# BLE.net
KiCad netlist of a schematic drawn in Altium Designer
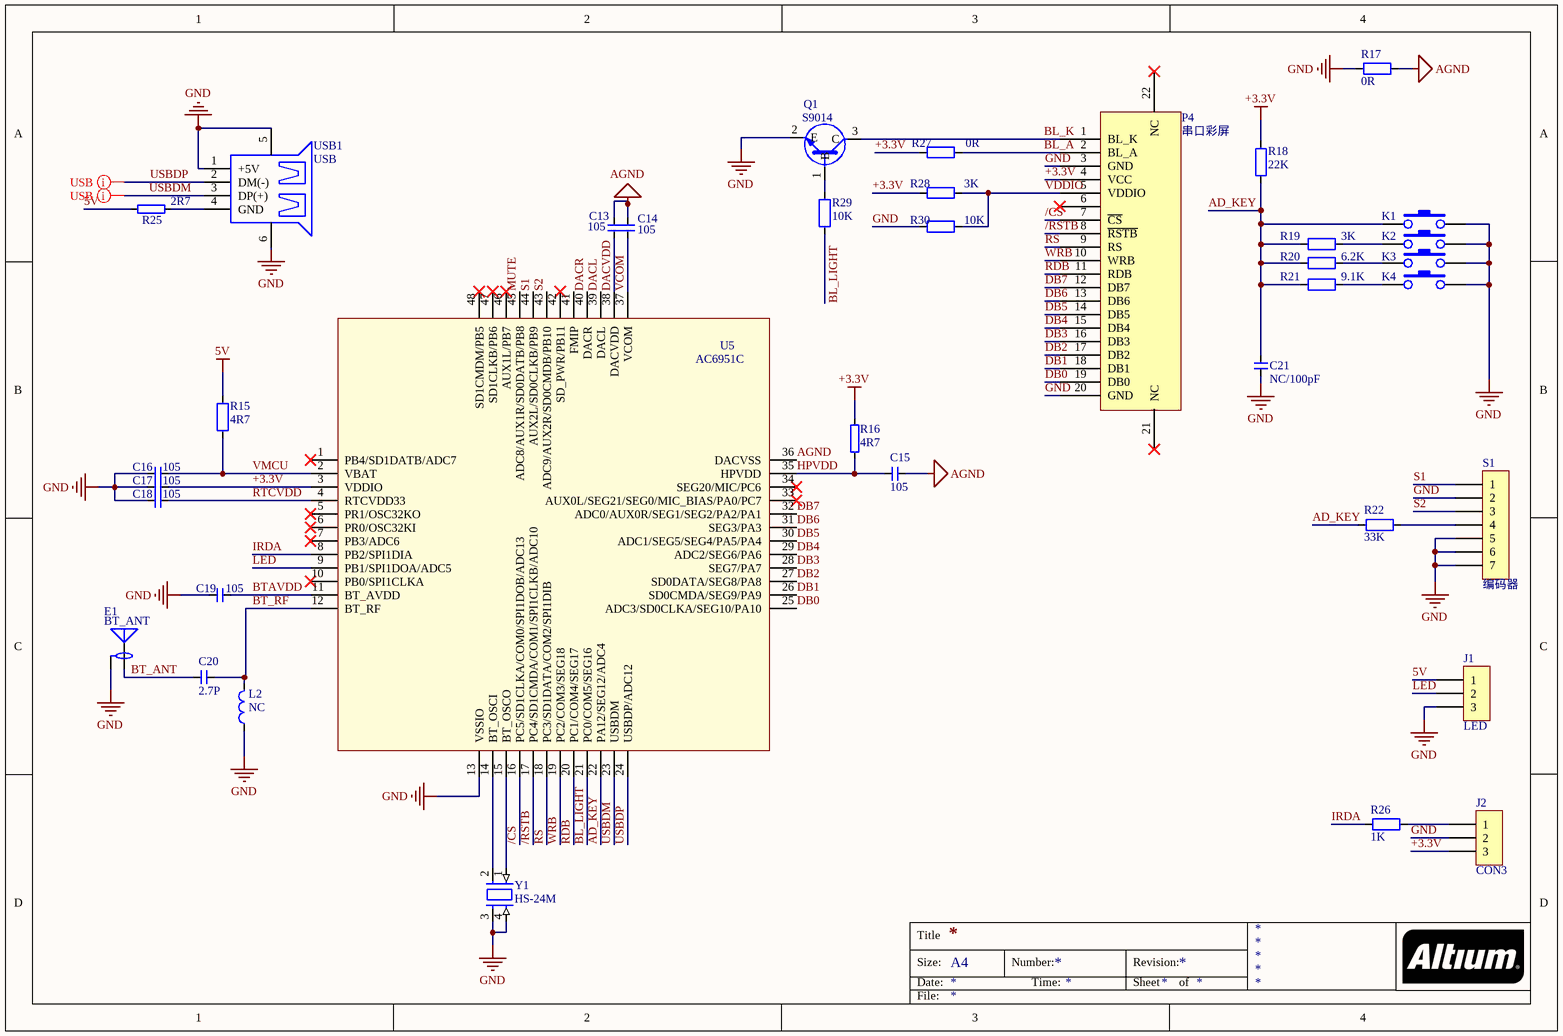
[diagram p0: BLE主控原理图.SchDoc]

(export (version "E")
  (design (tool "Eeschema 10.0.6"))
  (components
    (comp (ref "C13") (value "105") (footprint "C0603") (libsource (lib "MY") (part "CAP-0603")))
    (comp (ref "C14") (value "105") (footprint "C0603") (libsource (lib "MY") (part "CAP-0603")))
    (comp (ref "C15") (value "105") (footprint "C0603") (libsource (lib "MY") (part "CAP-0603")))
    (comp (ref "C16") (value "105") (footprint "C0603") (libsource (lib "MY") (part "CAP-0603")))
    (comp (ref "C17") (value "105") (footprint "C0603") (libsource (lib "MY") (part "CAP-0603")))
    (comp (ref "C18") (value "105") (footprint "C0603") (libsource (lib "MY") (part "CAP-0603")))
    (comp (ref "C19") (value "105") (footprint "C0603") (libsource (lib "MY") (part "CAP-0603")))
    (comp (ref "C20") (value "2.7P") (footprint "C0603") (libsource (lib "MY") (part "CAP-0603")))
    (comp (ref "C21") (value "NC/100pF") (footprint "C0603") (libsource (lib "MY") (part "CAP-0603")))
    (comp (ref "E1") (value "BT_ANT") (footprint "新F天线") (libsource (lib "常用原理图库") (part "BT_ANT")))
    (comp (ref "J1")
      (value "LED")
      (footprint "CON-3X2.54")
      (description "Connector")
      (libsource (lib "插件") (part "CON3"))
    )
    (comp (ref "J2")
      (value "CON3")
      (footprint "CON-3X2.54")
      (description "Connector")
      (libsource (lib "插件") (part "CON3"))
    )
    (comp (ref "K1") (value "~") (footprint "KEY") (libsource (lib "MY") (part "Key")))
    (comp (ref "K2") (value "~") (footprint "KEY") (libsource (lib "MY") (part "Key")))
    (comp (ref "K3") (value "~") (footprint "KEY") (libsource (lib "MY") (part "Key")))
    (comp (ref "K4") (value "~") (footprint "KEY") (libsource (lib "MY") (part "Key")))
    (comp (ref "L2") (value "NC") (footprint "L0603") (libsource (lib "MY") (part "L")))
    (comp (ref "P4") (value "串口彩屏") (footprint "FFC-P20-1MM") (libsource (lib "MY") (part "LCD-20P")))
    (comp (ref "Q1") (value "S9014") (footprint "SOT23") (libsource (lib "MY") (part "NPN")))
    (comp (ref "R15") (value "4R7") (footprint "R0805") (libsource (lib "MY") (part "RES-0603")))
    (comp (ref "R16") (value "4R7") (footprint "R0603") (libsource (lib "电阻") (part "RES")))
    (comp (ref "R17") (value "0R") (footprint "R0603") (libsource (lib "MY") (part "RES-0603")))
    (comp (ref "R18") (value "22K") (footprint "R0603") (libsource (lib "MY") (part "RES-0603")))
    (comp (ref "R19") (value "3K") (footprint "R0603") (libsource (lib "MY") (part "RES-0603")))
    (comp (ref "R20") (value "6.2K") (footprint "R0603") (libsource (lib "MY") (part "RES-0603")))
    (comp (ref "R21") (value "9.1K") (footprint "R0603") (libsource (lib "MY") (part "RES-0603")))
    (comp (ref "R22") (value "33K") (footprint "R0603") (libsource (lib "MY") (part "RES-0603")))
    (comp (ref "R25") (value "2R7") (footprint "R0603") (libsource (lib "电阻") (part "RES")))
    (comp (ref "R26") (value "1K") (footprint "R0603") (libsource (lib "MY") (part "RES-0603")))
    (comp (ref "R27") (value "0R") (footprint "R0603") (libsource (lib "MY") (part "RES-0603")))
    (comp (ref "R28") (value "3K") (footprint "R0603") (libsource (lib "MY") (part "RES-0603")))
    (comp (ref "R29") (value "10K") (footprint "R0603") (libsource (lib "MY") (part "RES-0603")))
    (comp (ref "R30") (value "10K") (footprint "R0603") (libsource (lib "MY") (part "RES-0603")))
    (comp (ref "S1")
      (value "编码器")
      (footprint "BMQ+PUSH")
      (description "Connector")
      (libsource (lib "插件") (part "CON7"))
    )
    (comp (ref "U5") (value "AC6951C") (footprint "LQFP48") (libsource (lib "MY") (part "AC6951C")))
    (comp (ref "USB1") (value "USB") (footprint "USBSMT") (libsource (lib "常用原理图库") (part "USB")))
    (comp (ref "Y1") (value "HS-24M") (footprint "JZ") (libsource (lib "常用原理图库") (part "CRYSTAL")))
  )
  (nets
    (net (code "1") (name "+3.3V") (class "Default")
      (node (ref "C17") (pin "2") (pinfunction "2_2") (pintype "passive"))
      (node (ref "J2") (pin "3") (pinfunction "3_3") (pintype "passive"))
      (node (ref "P4") (pin "4") (pinfunction "VCC_4") (pintype "passive"))
      (node (ref "R16") (pin "2") (pinfunction "2_2") (pintype "passive"))
      (node (ref "R18") (pin "2") (pinfunction "2_2") (pintype "passive"))
      (node (ref "R27") (pin "1") (pinfunction "1_1") (pintype "passive"))
      (node (ref "R28") (pin "2") (pinfunction "2_2") (pintype "passive"))
      (node (ref "U5") (pin "3") (pinfunction "VDDIO_3") (pintype "passive"))
    )
    (net (code "2") (name "/AD_KEY") (class "Default")
      (node (ref "C21") (pin "1") (pinfunction "1_1") (pintype "passive"))
      (node (ref "K1") (pin "1") (pinfunction "1_1") (pintype "passive"))
      (node (ref "R18") (pin "1") (pinfunction "1_1") (pintype "passive"))
      (node (ref "R19") (pin "1") (pinfunction "1_1") (pintype "passive"))
      (node (ref "R20") (pin "1") (pinfunction "1_1") (pintype "passive"))
      (node (ref "R21") (pin "1") (pinfunction "1_1") (pintype "passive"))
      (node (ref "R22") (pin "1") (pinfunction "1_1") (pintype "passive"))
      (node (ref "U5") (pin "22") (pinfunction "PA12/SEG12/ADC4_22") (pintype "passive"))
    )
    (net (code "3") (name "/BL_A") (class "Default")
      (node (ref "P4") (pin "2") (pinfunction "BL_A_2") (pintype "passive"))
      (node (ref "R27") (pin "2") (pinfunction "2_2") (pintype "passive"))
    )
    (net (code "4") (name "/BL_K") (class "Default")
      (node (ref "P4") (pin "1") (pinfunction "BL_K_1") (pintype "passive"))
      (node (ref "Q1") (pin "3") (pinfunction "C_3") (pintype "passive"))
    )
    (net (code "5") (name "/BL_LIGHT") (class "Default")
      (node (ref "R29") (pin "1") (pinfunction "1_1") (pintype "passive"))
      (node (ref "U5") (pin "21") (pinfunction "PC0/COM5/SEG16_21") (pintype "passive"))
    )
    (net (code "6") (name "/BTAVDD") (class "Default")
      (node (ref "C19") (pin "2") (pinfunction "2_2") (pintype "passive"))
      (node (ref "U5") (pin "11") (pinfunction "BT_AVDD_11") (pintype "passive"))
    )
    (net (code "7") (name "/BT_ANT") (class "Default")
      (node (ref "C20") (pin "1") (pinfunction "1_1") (pintype "passive"))
      (node (ref "E1") (pin "1") (pinfunction "1_1") (pintype "passive"))
    )
    (net (code "8") (name "/BT_RF") (class "Default")
      (node (ref "C20") (pin "2") (pinfunction "2_2") (pintype "passive"))
      (node (ref "L2") (pin "2") (pinfunction "2_2") (pintype "passive"))
      (node (ref "U5") (pin "12") (pinfunction "BT_RF_12") (pintype "passive"))
    )
    (net (code "9") (name "/DACL") (class "Default")
      (node (ref "U5") (pin "39") (pinfunction "DACL_39") (pintype "passive"))
    )
    (net (code "10") (name "/DACR") (class "Default")
      (node (ref "U5") (pin "40") (pinfunction "DACR_40") (pintype "passive"))
    )
    (net (code "11") (name "/DACVDD") (class "Default")
      (node (ref "C13") (pin "1") (pinfunction "1_1") (pintype "passive"))
      (node (ref "U5") (pin "38") (pinfunction "DACVDD_38") (pintype "passive"))
    )
    (net (code "12") (name "/DB0") (class "Default")
      (node (ref "P4") (pin "19") (pinfunction "DB0_19") (pintype "passive"))
      (node (ref "U5") (pin "25") (pinfunction "ADC3/SD0CLKA/SEG10/PA10_25") (pintype "passive"))
    )
    (net (code "13") (name "/DB1") (class "Default")
      (node (ref "P4") (pin "18") (pinfunction "DB1_18") (pintype "passive"))
      (node (ref "U5") (pin "26") (pinfunction "SD0CMDA/SEG9/PA9_26") (pintype "passive"))
    )
    (net (code "14") (name "/DB2") (class "Default")
      (node (ref "P4") (pin "17") (pinfunction "DB2_17") (pintype "passive"))
      (node (ref "U5") (pin "27") (pinfunction "SD0DATA/SEG8/PA8_27") (pintype "passive"))
    )
    (net (code "15") (name "/DB3") (class "Default")
      (node (ref "P4") (pin "16") (pinfunction "DB3_16") (pintype "passive"))
      (node (ref "U5") (pin "28") (pinfunction "SEG7/PA7_28") (pintype "passive"))
    )
    (net (code "16") (name "/DB4") (class "Default")
      (node (ref "P4") (pin "15") (pinfunction "DB4_15") (pintype "passive"))
      (node (ref "U5") (pin "29") (pinfunction "ADC2/SEG6/PA6_29") (pintype "passive"))
    )
    (net (code "17") (name "/DB5") (class "Default")
      (node (ref "P4") (pin "14") (pinfunction "DB5_14") (pintype "passive"))
      (node (ref "U5") (pin "30") (pinfunction "ADC1/SEG5/SEG4/PA5/PA4_30") (pintype "passive"))
    )
    (net (code "18") (name "/DB6") (class "Default")
      (node (ref "P4") (pin "13") (pinfunction "DB6_13") (pintype "passive"))
      (node (ref "U5") (pin "31") (pinfunction "SEG3/PA3_31") (pintype "passive"))
    )
    (net (code "19") (name "/DB7") (class "Default")
      (node (ref "P4") (pin "12") (pinfunction "DB7_12") (pintype "passive"))
      (node (ref "U5") (pin "32") (pinfunction "ADC0/AUX0R/SEG1/SEG2/PA2/PA1_32") (pintype "passive"))
    )
    (net (code "20") (name "/HPVDD") (class "Default")
      (node (ref "C15") (pin "2") (pinfunction "2_2") (pintype "passive"))
      (node (ref "R16") (pin "1") (pinfunction "1_1") (pintype "passive"))
      (node (ref "U5") (pin "35") (pinfunction "HPVDD_35") (pintype "passive"))
    )
    (net (code "21") (name "/IRDA") (class "Default")
      (node (ref "R26") (pin "1") (pinfunction "1_1") (pintype "passive"))
      (node (ref "U5") (pin "8") (pinfunction "PB2/SPI1DIA_8") (pintype "passive"))
    )
    (net (code "22") (name "/LED") (class "Default")
      (node (ref "J1") (pin "2") (pinfunction "2_2") (pintype "passive"))
      (node (ref "U5") (pin "9") (pinfunction "PB1/SPI1DOA/ADC5_9") (pintype "passive"))
    )
    (net (code "23") (name "/MUTE") (class "Default")
      (node (ref "U5") (pin "45") (pinfunction "ADC8/AUX1R/SD0DATB/PB8_45") (pintype "passive"))
    )
    (net (code "24") (name "/RDB") (class "Default")
      (node (ref "P4") (pin "11") (pinfunction "RDB_11") (pintype "passive"))
      (node (ref "U5") (pin "20") (pinfunction "PC1/COM4/SEG17_20") (pintype "passive"))
    )
    (net (code "25") (name "/RS") (class "Default")
      (node (ref "P4") (pin "9") (pinfunction "RS_9") (pintype "passive"))
      (node (ref "U5") (pin "18") (pinfunction "PC3/SD1DATA/COM2/SPI1DIB_18") (pintype "passive"))
    )
    (net (code "26") (name "/RTCVDD") (class "Default")
      (node (ref "C18") (pin "2") (pinfunction "2_2") (pintype "passive"))
      (node (ref "U5") (pin "4") (pinfunction "RTCVDD33_4") (pintype "passive"))
    )
    (net (code "27") (name "/S1") (class "Default")
      (node (ref "S1") (pin "1") (pinfunction "1_1") (pintype "passive"))
      (node (ref "U5") (pin "44") (pinfunction "AUX2L/SD0CLKB/PB9_44") (pintype "passive"))
    )
    (net (code "28") (name "/S2") (class "Default")
      (node (ref "S1") (pin "3") (pinfunction "3_3") (pintype "passive"))
      (node (ref "U5") (pin "43") (pinfunction "ADC9/AUX2R/SD0CMDB/PB10_43") (pintype "passive"))
    )
    (net (code "29") (name "/USBDM") (class "Default")
      (node (ref "U5") (pin "23") (pinfunction "USBDM_23") (pintype "passive"))
      (node (ref "USB1") (pin "3") (pinfunction "DP(+)_3") (pintype "passive"))
    )
    (net (code "30") (name "/USBDP") (class "Default")
      (node (ref "U5") (pin "24") (pinfunction "USBDP/ADC12_24") (pintype "passive"))
      (node (ref "USB1") (pin "2") (pinfunction "DM(-)_2") (pintype "passive"))
    )
    (net (code "31") (name "/VCOM") (class "Default")
      (node (ref "C14") (pin "1") (pinfunction "1_1") (pintype "passive"))
      (node (ref "U5") (pin "37") (pinfunction "VCOM_37") (pintype "passive"))
    )
    (net (code "32") (name "/VDDIO") (class "Default")
      (node (ref "P4") (pin "5") (pinfunction "VDDIO_5") (pintype "passive"))
      (node (ref "R28") (pin "1") (pinfunction "1_1") (pintype "passive"))
      (node (ref "R30") (pin "1") (pinfunction "1_1") (pintype "passive"))
    )
    (net (code "33") (name "/VMCU") (class "Default")
      (node (ref "C16") (pin "2") (pinfunction "2_2") (pintype "passive"))
      (node (ref "R15") (pin "2") (pinfunction "2_2") (pintype "passive"))
      (node (ref "U5") (pin "2") (pinfunction "VBAT_2") (pintype "passive"))
    )
    (net (code "34") (name "/WRB") (class "Default")
      (node (ref "P4") (pin "10") (pinfunction "WRB_10") (pintype "passive"))
      (node (ref "U5") (pin "19") (pinfunction "PC2/COM3/SEG18_19") (pintype "passive"))
    )
    (net (code "35") (name "/{slash}CS") (class "Default")
      (node (ref "P4") (pin "7") (pinfunction "~{CS}_7") (pintype "passive"))
      (node (ref "U5") (pin "16") (pinfunction "PC5/SD1CLKA/COM0/SPI1DOB/ADC13_16") (pintype "passive"))
    )
    (net (code "36") (name "/{slash}RSTB") (class "Default")
      (node (ref "P4") (pin "8") (pinfunction "~{RSTB}_8") (pintype "passive"))
      (node (ref "U5") (pin "17") (pinfunction "PC4/SD1CMDA/COM1/SPI1CLKB/ADC10_17") (pintype "passive"))
    )
    (net (code "37") (name "5V") (class "Default")
      (node (ref "J1") (pin "1") (pinfunction "1_1") (pintype "passive"))
      (node (ref "R15") (pin "1") (pinfunction "1_1") (pintype "passive"))
      (node (ref "R25") (pin "1") (pinfunction "1_1") (pintype "passive"))
    )
    (net (code "38") (name "AGND") (class "Default")
      (node (ref "C13") (pin "2") (pinfunction "2_2") (pintype "passive"))
      (node (ref "C14") (pin "2") (pinfunction "2_2") (pintype "passive"))
      (node (ref "C15") (pin "1") (pinfunction "1_1") (pintype "passive"))
      (node (ref "R17") (pin "2") (pinfunction "2_2") (pintype "passive"))
      (node (ref "U5") (pin "36") (pinfunction "DACVSS_36") (pintype "passive"))
    )
    (net (code "39") (name "GND") (class "Default")
      (node (ref "C16") (pin "1") (pinfunction "1_1") (pintype "passive"))
      (node (ref "C17") (pin "1") (pinfunction "1_1") (pintype "passive"))
      (node (ref "C18") (pin "1") (pinfunction "1_1") (pintype "passive"))
      (node (ref "C19") (pin "1") (pinfunction "1_1") (pintype "passive"))
      (node (ref "C21") (pin "2") (pinfunction "2_2") (pintype "passive"))
      (node (ref "E1") (pin "2") (pinfunction "2_2") (pintype "passive"))
      (node (ref "J1") (pin "3") (pinfunction "3_3") (pintype "passive"))
      (node (ref "J2") (pin "2") (pinfunction "2_2") (pintype "passive"))
      (node (ref "K1") (pin "2") (pinfunction "2_2") (pintype "passive"))
      (node (ref "K2") (pin "2") (pinfunction "2_2") (pintype "passive"))
      (node (ref "K3") (pin "2") (pinfunction "2_2") (pintype "passive"))
      (node (ref "K4") (pin "2") (pinfunction "2_2") (pintype "passive"))
      (node (ref "L2") (pin "1") (pinfunction "1_1") (pintype "passive"))
      (node (ref "P4") (pin "20") (pinfunction "GND_20") (pintype "passive"))
      (node (ref "P4") (pin "3") (pinfunction "GND_3") (pintype "passive"))
      (node (ref "Q1") (pin "2") (pinfunction "E_2") (pintype "passive"))
      (node (ref "R17") (pin "1") (pinfunction "1_1") (pintype "passive"))
      (node (ref "R30") (pin "2") (pinfunction "2_2") (pintype "passive"))
      (node (ref "S1") (pin "2") (pinfunction "2_2") (pintype "passive"))
      (node (ref "S1") (pin "5") (pinfunction "5_5") (pintype "passive"))
      (node (ref "S1") (pin "6") (pinfunction "6_6") (pintype "passive"))
      (node (ref "S1") (pin "7") (pinfunction "7_7") (pintype "passive"))
      (node (ref "U5") (pin "13") (pinfunction "VSSIO_13") (pintype "passive"))
      (node (ref "USB1") (pin "1") (pinfunction "+5V_1") (pintype "passive"))
      (node (ref "USB1") (pin "5") (pinfunction "5_5") (pintype "passive"))
      (node (ref "USB1") (pin "6") (pinfunction "6_6") (pintype "passive"))
      (node (ref "Y1") (pin "3") (pinfunction "3_3") (pintype "passive"))
      (node (ref "Y1") (pin "4") (pinfunction "4_4") (pintype "input"))
    )
    (net (code "40") (name "Net-(J2-Pad1)") (class "Default")
      (node (ref "J2") (pin "1") (pinfunction "1_1") (pintype "passive"))
      (node (ref "R26") (pin "2") (pinfunction "2_2") (pintype "passive"))
    )
    (net (code "41") (name "Net-(K2-Pad1)") (class "Default")
      (node (ref "K2") (pin "1") (pinfunction "1_1") (pintype "passive"))
      (node (ref "R19") (pin "2") (pinfunction "2_2") (pintype "passive"))
    )
    (net (code "42") (name "Net-(K3-Pad1)") (class "Default")
      (node (ref "K3") (pin "1") (pinfunction "1_1") (pintype "passive"))
      (node (ref "R20") (pin "2") (pinfunction "2_2") (pintype "passive"))
    )
    (net (code "43") (name "Net-(K4-Pad1)") (class "Default")
      (node (ref "K4") (pin "1") (pinfunction "1_1") (pintype "passive"))
      (node (ref "R21") (pin "2") (pinfunction "2_2") (pintype "passive"))
    )
    (net (code "44") (name "Net-(Q1-B)") (class "Default")
      (node (ref "Q1") (pin "1") (pinfunction "B_1") (pintype "passive"))
      (node (ref "R29") (pin "2") (pinfunction "2_2") (pintype "passive"))
    )
    (net (code "45") (name "Net-(R22-Pad2)") (class "Default")
      (node (ref "R22") (pin "2") (pinfunction "2_2") (pintype "passive"))
      (node (ref "S1") (pin "4") (pinfunction "4_4") (pintype "passive"))
    )
    (net (code "46") (name "Net-(U5-BT_OSCI)") (class "Default")
      (node (ref "U5") (pin "14") (pinfunction "BT_OSCI_14") (pintype "passive"))
      (node (ref "Y1") (pin "2") (pinfunction "2_2") (pintype "passive"))
    )
    (net (code "47") (name "Net-(U5-BT_OSCO)") (class "Default")
      (node (ref "U5") (pin "15") (pinfunction "BT_OSCO_15") (pintype "passive"))
      (node (ref "Y1") (pin "1") (pinfunction "1_1") (pintype "input"))
    )
    (net (code "48") (name "Net-(USB1-GND)") (class "Default")
      (node (ref "R25") (pin "2") (pinfunction "2_2") (pintype "passive"))
      (node (ref "USB1") (pin "4") (pinfunction "GND_4") (pintype "passive"))
    )
    (net (code "49") (name "unconnected-(P4-NC-Pad21)") (class "Default")
      (node (ref "P4") (pin "21") (pinfunction "NC_21") (pintype "passive+no_connect"))
    )
    (net (code "50") (name "unconnected-(P4-NC-Pad22)") (class "Default")
      (node (ref "P4") (pin "22") (pinfunction "NC_22") (pintype "passive+no_connect"))
    )
    (net (code "51") (name "unconnected-(P4-Pad6)") (class "Default")
      (node (ref "P4") (pin "6") (pintype "passive+no_connect"))
    )
    (net (code "52") (name "unconnected-(U5-AUX0L{slash}SEG21{slash}SEG0{slash}MIC_BIAS{slash}PA0{slash}PC7-Pad33)") (class "Default")
      (node (ref "U5") (pin "33") (pinfunction "AUX0L/SEG21/SEG0/MIC_BIAS/PA0/PC7_33") (pintype "passive+no_connect"))
    )
    (net (code "53") (name "unconnected-(U5-AUX1L{slash}PB7-Pad46)") (class "Default")
      (node (ref "U5") (pin "46") (pinfunction "AUX1L/PB7_46") (pintype "passive+no_connect"))
    )
    (net (code "54") (name "unconnected-(U5-FMIP-Pad41)") (class "Default")
      (node (ref "U5") (pin "41") (pinfunction "FMIP_41") (pintype "passive"))
    )
    (net (code "55") (name "unconnected-(U5-PB0{slash}SPI1CLKA-Pad10)") (class "Default")
      (node (ref "U5") (pin "10") (pinfunction "PB0/SPI1CLKA_10") (pintype "passive+no_connect"))
    )
    (net (code "56") (name "unconnected-(U5-PB3{slash}ADC6-Pad7)") (class "Default")
      (node (ref "U5") (pin "7") (pinfunction "PB3/ADC6_7") (pintype "passive+no_connect"))
    )
    (net (code "57") (name "unconnected-(U5-PB4{slash}SD1DATB{slash}ADC7-Pad1)") (class "Default")
      (node (ref "U5") (pin "1") (pinfunction "PB4/SD1DATB/ADC7_1") (pintype "passive+no_connect"))
    )
    (net (code "58") (name "unconnected-(U5-PR0{slash}OSC32KI-Pad6)") (class "Default")
      (node (ref "U5") (pin "6") (pinfunction "PR0/OSC32KI_6") (pintype "passive+no_connect"))
    )
    (net (code "59") (name "unconnected-(U5-PR1{slash}OSC32KO-Pad5)") (class "Default")
      (node (ref "U5") (pin "5") (pinfunction "PR1/OSC32KO_5") (pintype "passive+no_connect"))
    )
    (net (code "60") (name "unconnected-(U5-SD1CLKB{slash}PB6-Pad47)") (class "Default")
      (node (ref "U5") (pin "47") (pinfunction "SD1CLKB/PB6_47") (pintype "passive+no_connect"))
    )
    (net (code "61") (name "unconnected-(U5-SD1CMDM{slash}PB5-Pad48)") (class "Default")
      (node (ref "U5") (pin "48") (pinfunction "SD1CMDM/PB5_48") (pintype "passive+no_connect"))
    )
    (net (code "62") (name "unconnected-(U5-SD_PWR{slash}PB11-Pad42)") (class "Default")
      (node (ref "U5") (pin "42") (pinfunction "SD_PWR/PB11_42") (pintype "passive+no_connect"))
    )
    (net (code "63") (name "unconnected-(U5-SEG20{slash}MIC{slash}PC6-Pad34)") (class "Default")
      (node (ref "U5") (pin "34") (pinfunction "SEG20/MIC/PC6_34") (pintype "passive+no_connect"))
    )
  )
)
